# Sheet3.net
KiCad netlist of a schematic drawn in Altium Designer
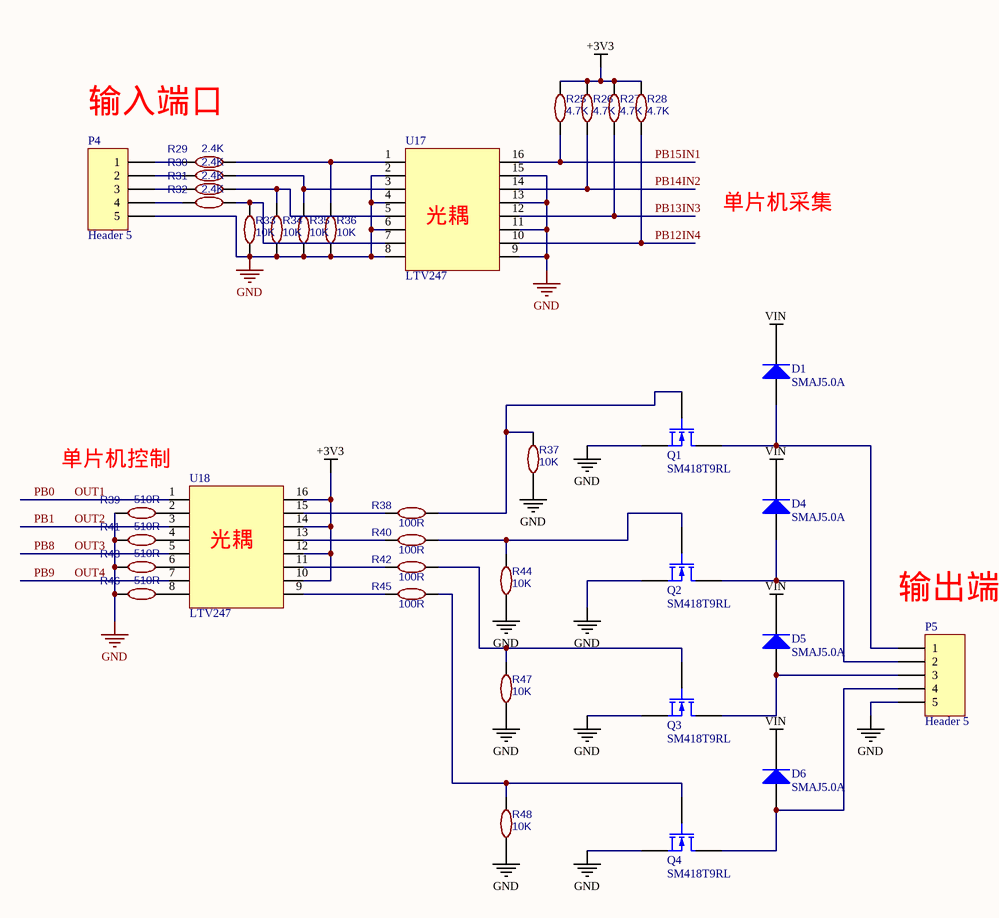
[diagram p0: Sheet3.SchDoc]

(export (version "E")
  (design (tool "Eeschema 10.0.6"))
  (components
    (comp (ref "D1")
      (value "SMAJ5.0A")
      (footprint "DO214-SMA-SOAC")
      (description "Default Diode")
      (fields (field (name "PUBLISHER") "Altium Limited"))
      (libsource (lib "Miscellaneous Devices") (part "Diode"))
    )
    (comp (ref "D4")
      (value "SMAJ5.0A")
      (footprint "DO214-SMA-SOAC")
      (description "Default Diode")
      (fields (field (name "PUBLISHER") "Altium Limited"))
      (libsource (lib "Miscellaneous Devices") (part "Diode"))
    )
    (comp (ref "D5")
      (value "SMAJ5.0A")
      (footprint "DO214-SMA-SOAC")
      (description "Default Diode")
      (fields (field (name "PUBLISHER") "Altium Limited"))
      (libsource (lib "Miscellaneous Devices") (part "Diode"))
    )
    (comp (ref "D6")
      (value "SMAJ5.0A")
      (footprint "DO214-SMA-SOAC")
      (description "Default Diode")
      (fields (field (name "PUBLISHER") "Altium Limited"))
      (libsource (lib "Miscellaneous Devices") (part "Diode"))
    )
    (comp (ref "P4")
      (value "Header 5")
      (footprint "HDR1X5")
      (description "Header, 5-Pin 隔离输入输出5P")
      (fields (field (name "PUBLISHER") "Altium Limited"))
      (libsource (lib "") (part "Header 5_1"))
    )
    (comp (ref "P5")
      (value "Header 5")
      (footprint "HDR1X5")
      (description "Header, 5-Pin 隔离输入输出5P")
      (fields (field (name "PUBLISHER") "Altium Limited"))
      (libsource (lib "Miscellaneous Connectors") (part "Header 5"))
    )
    (comp (ref "Q1")
      (value "SM418T9RL")
      (footprint "TO252-3")
      (description "N-Channel MOSFET")
      (fields (field (name "PUBLISHER") "Altium Limited"))
      (libsource (lib "Miscellaneous Devices") (part "MOSFET-N"))
    )
    (comp (ref "Q2")
      (value "SM418T9RL")
      (footprint "TO252-3")
      (description "N-Channel MOSFET")
      (fields (field (name "PUBLISHER") "Altium Limited"))
      (libsource (lib "Miscellaneous Devices") (part "MOSFET-N"))
    )
    (comp (ref "Q3")
      (value "SM418T9RL")
      (footprint "TO252-3")
      (description "N-Channel MOSFET")
      (fields (field (name "PUBLISHER") "Altium Limited"))
      (libsource (lib "Miscellaneous Devices") (part "MOSFET-N"))
    )
    (comp (ref "Q4")
      (value "SM418T9RL")
      (footprint "TO252-3")
      (description "N-Channel MOSFET")
      (fields (field (name "PUBLISHER") "Altium Limited"))
      (libsource (lib "Miscellaneous Devices") (part "MOSFET-N"))
    )
    (comp (ref "R25")
      (value "4.7K")
      (footprint "R0603")
      (fields
        (field (name "BOM_MANUFACTURER PART") "0603WAF1001T5E")
        (field (name "BOM_SUPPLIER PART") "C21190")
      )
      (libsource (lib "altium-import") (part "root_1_1K_"))
    )
    (comp (ref "R26")
      (value "4.7K")
      (footprint "R0603")
      (fields
        (field (name "BOM_MANUFACTURER PART") "0603WAF1001T5E")
        (field (name "BOM_SUPPLIER PART") "C21190")
      )
      (libsource (lib "altium-import") (part "root_1_1K_"))
    )
    (comp (ref "R27")
      (value "4.7K")
      (footprint "R0603")
      (fields
        (field (name "BOM_MANUFACTURER PART") "0603WAF1001T5E")
        (field (name "BOM_SUPPLIER PART") "C21190")
      )
      (libsource (lib "altium-import") (part "root_1_1K_"))
    )
    (comp (ref "R28")
      (value "4.7K")
      (footprint "R0603")
      (fields
        (field (name "BOM_MANUFACTURER PART") "0603WAF1001T5E")
        (field (name "BOM_SUPPLIER PART") "C21190")
      )
      (libsource (lib "altium-import") (part "root_1_1K_"))
    )
    (comp (ref "R29")
      (value "2.4K")
      (footprint "R0603")
      (fields
        (field (name "BOM_MANUFACTURER PART") "0603WAF1001T5E")
        (field (name "BOM_SUPPLIER PART") "C21190")
      )
      (libsource (lib "altium-import") (part "root_0_1K_"))
    )
    (comp (ref "R30")
      (value "2.4K")
      (footprint "R0603")
      (fields
        (field (name "BOM_MANUFACTURER PART") "0603WAF1001T5E")
        (field (name "BOM_SUPPLIER PART") "C21190")
      )
      (libsource (lib "altium-import") (part "root_0_1K_"))
    )
    (comp (ref "R31")
      (value "2.4K")
      (footprint "R0603")
      (fields
        (field (name "BOM_MANUFACTURER PART") "0603WAF1001T5E")
        (field (name "BOM_SUPPLIER PART") "C21190")
      )
      (libsource (lib "altium-import") (part "root_0_1K_"))
    )
    (comp (ref "R32")
      (value "2.4K")
      (footprint "R0603")
      (fields
        (field (name "BOM_MANUFACTURER PART") "0603WAF1001T5E")
        (field (name "BOM_SUPPLIER PART") "C21190")
      )
      (libsource (lib "altium-import") (part "root_0_1K_"))
    )
    (comp (ref "R33")
      (value "10K")
      (footprint "R0603")
      (fields
        (field (name "BOM_MANUFACTURER PART") "0603WAF1001T5E")
        (field (name "BOM_SUPPLIER PART") "C21190")
      )
      (libsource (lib "altium-import") (part "root_1_1K_"))
    )
    (comp (ref "R34")
      (value "10K")
      (footprint "R0603")
      (fields
        (field (name "BOM_MANUFACTURER PART") "0603WAF1001T5E")
        (field (name "BOM_SUPPLIER PART") "C21190")
      )
      (libsource (lib "altium-import") (part "root_1_1K_"))
    )
    (comp (ref "R35")
      (value "10K")
      (footprint "R0603")
      (fields
        (field (name "BOM_MANUFACTURER PART") "0603WAF1001T5E")
        (field (name "BOM_SUPPLIER PART") "C21190")
      )
      (libsource (lib "altium-import") (part "root_1_1K_"))
    )
    (comp (ref "R36")
      (value "10K")
      (footprint "R0603")
      (fields
        (field (name "BOM_MANUFACTURER PART") "0603WAF1001T5E")
        (field (name "BOM_SUPPLIER PART") "C21190")
      )
      (libsource (lib "altium-import") (part "root_1_1K_"))
    )
    (comp (ref "R37")
      (value "10K")
      (footprint "R0603")
      (fields
        (field (name "BOM_MANUFACTURER PART") "0603WAF1001T5E")
        (field (name "BOM_SUPPLIER PART") "C21190")
      )
      (libsource (lib "altium-import") (part "root_3_1K_"))
    )
    (comp (ref "R38")
      (value "100R")
      (footprint "R0603")
      (fields
        (field (name "BOM_MANUFACTURER PART") "0603WAF1001T5E")
        (field (name "BOM_SUPPLIER PART") "C21190")
      )
      (libsource (lib "altium-import") (part "root_0_1K_"))
    )
    (comp (ref "R39")
      (value "510R")
      (footprint "R0603")
      (fields
        (field (name "BOM_MANUFACTURER PART") "0603WAF1001T5E")
        (field (name "BOM_SUPPLIER PART") "C21190")
      )
      (libsource (lib "altium-import") (part "root_0_1K_"))
    )
    (comp (ref "R40")
      (value "100R")
      (footprint "R0603")
      (fields
        (field (name "BOM_MANUFACTURER PART") "0603WAF1001T5E")
        (field (name "BOM_SUPPLIER PART") "C21190")
      )
      (libsource (lib "altium-import") (part "root_0_1K_"))
    )
    (comp (ref "R41")
      (value "510R")
      (footprint "R0603")
      (fields
        (field (name "BOM_MANUFACTURER PART") "0603WAF1001T5E")
        (field (name "BOM_SUPPLIER PART") "C21190")
      )
      (libsource (lib "altium-import") (part "root_0_1K_"))
    )
    (comp (ref "R42")
      (value "100R")
      (footprint "R0603")
      (fields
        (field (name "BOM_MANUFACTURER PART") "0603WAF1001T5E")
        (field (name "BOM_SUPPLIER PART") "C21190")
      )
      (libsource (lib "altium-import") (part "root_0_1K_"))
    )
    (comp (ref "R43")
      (value "510R")
      (footprint "R0603")
      (fields
        (field (name "BOM_MANUFACTURER PART") "0603WAF1001T5E")
        (field (name "BOM_SUPPLIER PART") "C21190")
      )
      (libsource (lib "altium-import") (part "root_0_1K_"))
    )
    (comp (ref "R44")
      (value "10K")
      (footprint "R0603")
      (fields
        (field (name "BOM_MANUFACTURER PART") "0603WAF1001T5E")
        (field (name "BOM_SUPPLIER PART") "C21190")
      )
      (libsource (lib "altium-import") (part "root_3_1K_"))
    )
    (comp (ref "R45")
      (value "100R")
      (footprint "R0603")
      (fields
        (field (name "BOM_MANUFACTURER PART") "0603WAF1001T5E")
        (field (name "BOM_SUPPLIER PART") "C21190")
      )
      (libsource (lib "altium-import") (part "root_0_1K_"))
    )
    (comp (ref "R46")
      (value "510R")
      (footprint "R0603")
      (fields
        (field (name "BOM_MANUFACTURER PART") "0603WAF1001T5E")
        (field (name "BOM_SUPPLIER PART") "C21190")
      )
      (libsource (lib "altium-import") (part "root_0_1K_"))
    )
    (comp (ref "R47")
      (value "10K")
      (footprint "R0603")
      (fields
        (field (name "BOM_MANUFACTURER PART") "0603WAF1001T5E")
        (field (name "BOM_SUPPLIER PART") "C21190")
      )
      (libsource (lib "altium-import") (part "root_3_1K_"))
    )
    (comp (ref "R48")
      (value "10K")
      (footprint "R0603")
      (fields
        (field (name "BOM_MANUFACTURER PART") "0603WAF1001T5E")
        (field (name "BOM_SUPPLIER PART") "C21190")
      )
      (libsource (lib "altium-import") (part "root_3_1K_"))
    )
    (comp (ref "U17")
      (value "LTV247")
      (footprint "SOIC-16-M")
      (description "光耦")
      (libsource (lib "PCB_原理图库") (part "SOP-16"))
    )
    (comp (ref "U18")
      (value "LTV247")
      (footprint "SOIC-16-M")
      (description "光耦")
      (libsource (lib "PCB_原理图库") (part "SOP-16"))
    )
  )
  (nets
    (net (code "1") (name "+3V3") (class "Default")
      (node (ref "R25") (pin "2") (pinfunction "2_2") (pintype "passive"))
      (node (ref "R26") (pin "2") (pinfunction "2_2") (pintype "passive"))
      (node (ref "R27") (pin "2") (pinfunction "2_2") (pintype "passive"))
      (node (ref "R28") (pin "2") (pinfunction "2_2") (pintype "passive"))
      (node (ref "U18") (pin "10") (pinfunction "10_10") (pintype "passive"))
      (node (ref "U18") (pin "12") (pinfunction "12_12") (pintype "passive"))
      (node (ref "U18") (pin "14") (pinfunction "14_14") (pintype "passive"))
      (node (ref "U18") (pin "16") (pinfunction "16_16") (pintype "passive"))
    )
    (net (code "2") (name "/IN1") (class "Default")
      (node (ref "R25") (pin "1") (pinfunction "1_1") (pintype "passive"))
      (node (ref "U17") (pin "16") (pinfunction "16_16") (pintype "passive"))
    )
    (net (code "3") (name "/IN2") (class "Default")
      (node (ref "R26") (pin "1") (pinfunction "1_1") (pintype "passive"))
      (node (ref "U17") (pin "14") (pinfunction "14_14") (pintype "passive"))
    )
    (net (code "4") (name "/IN3") (class "Default")
      (node (ref "R27") (pin "1") (pinfunction "1_1") (pintype "passive"))
      (node (ref "U17") (pin "12") (pinfunction "12_12") (pintype "passive"))
    )
    (net (code "5") (name "/IN4") (class "Default")
      (node (ref "R28") (pin "1") (pinfunction "1_1") (pintype "passive"))
      (node (ref "U17") (pin "10") (pinfunction "10_10") (pintype "passive"))
    )
    (net (code "6") (name "/OUT1") (class "Default")
      (node (ref "U18") (pin "1") (pinfunction "1_1") (pintype "passive"))
    )
    (net (code "7") (name "/OUT2") (class "Default")
      (node (ref "U18") (pin "3") (pinfunction "3_3") (pintype "passive"))
    )
    (net (code "8") (name "/OUT3") (class "Default")
      (node (ref "U18") (pin "5") (pinfunction "5_5") (pintype "passive"))
    )
    (net (code "9") (name "/OUT4") (class "Default")
      (node (ref "U18") (pin "7") (pinfunction "7_7") (pintype "passive"))
    )
    (net (code "10") (name "GND") (class "Default")
      (node (ref "P4") (pin "5") (pinfunction "5_5") (pintype "passive"))
      (node (ref "P5") (pin "5") (pinfunction "5_5") (pintype "passive"))
      (node (ref "Q1") (pin "3") (pinfunction "S_3") (pintype "passive"))
      (node (ref "Q2") (pin "3") (pinfunction "S_3") (pintype "passive"))
      (node (ref "Q3") (pin "3") (pinfunction "S_3") (pintype "passive"))
      (node (ref "Q4") (pin "3") (pinfunction "S_3") (pintype "passive"))
      (node (ref "R33") (pin "1") (pinfunction "1_1") (pintype "passive"))
      (node (ref "R34") (pin "1") (pinfunction "1_1") (pintype "passive"))
      (node (ref "R35") (pin "1") (pinfunction "1_1") (pintype "passive"))
      (node (ref "R36") (pin "1") (pinfunction "1_1") (pintype "passive"))
      (node (ref "R37") (pin "2") (pinfunction "2_2") (pintype "passive"))
      (node (ref "R39") (pin "1") (pinfunction "1_1") (pintype "passive"))
      (node (ref "R41") (pin "1") (pinfunction "1_1") (pintype "passive"))
      (node (ref "R43") (pin "1") (pinfunction "1_1") (pintype "passive"))
      (node (ref "R44") (pin "2") (pinfunction "2_2") (pintype "passive"))
      (node (ref "R46") (pin "1") (pinfunction "1_1") (pintype "passive"))
      (node (ref "R47") (pin "2") (pinfunction "2_2") (pintype "passive"))
      (node (ref "R48") (pin "2") (pinfunction "2_2") (pintype "passive"))
      (node (ref "U17") (pin "11") (pinfunction "11_11") (pintype "passive"))
      (node (ref "U17") (pin "13") (pinfunction "13_13") (pintype "passive"))
      (node (ref "U17") (pin "15") (pinfunction "15_15") (pintype "passive"))
      (node (ref "U17") (pin "2") (pinfunction "2_2") (pintype "passive"))
      (node (ref "U17") (pin "4") (pinfunction "4_4") (pintype "passive"))
      (node (ref "U17") (pin "6") (pinfunction "6_6") (pintype "passive"))
      (node (ref "U17") (pin "8") (pinfunction "8_8") (pintype "passive"))
      (node (ref "U17") (pin "9") (pinfunction "9_9") (pintype "passive"))
    )
    (net (code "11") (name "Net-(D1-A)") (class "Default")
      (node (ref "D1") (pin "1") (pinfunction "A_1") (pintype "passive"))
      (node (ref "P5") (pin "1") (pinfunction "1_1") (pintype "passive"))
      (node (ref "Q1") (pin "1") (pinfunction "D_1") (pintype "passive"))
    )
    (net (code "12") (name "Net-(D4-A)") (class "Default")
      (node (ref "D4") (pin "1") (pinfunction "A_1") (pintype "passive"))
      (node (ref "P5") (pin "2") (pinfunction "2_2") (pintype "passive"))
      (node (ref "Q2") (pin "1") (pinfunction "D_1") (pintype "passive"))
    )
    (net (code "13") (name "Net-(D5-A)") (class "Default")
      (node (ref "D5") (pin "1") (pinfunction "A_1") (pintype "passive"))
      (node (ref "P5") (pin "3") (pinfunction "3_3") (pintype "passive"))
      (node (ref "Q3") (pin "1") (pinfunction "D_1") (pintype "passive"))
    )
    (net (code "14") (name "Net-(D6-A)") (class "Default")
      (node (ref "D6") (pin "1") (pinfunction "A_1") (pintype "passive"))
      (node (ref "P5") (pin "4") (pinfunction "4_4") (pintype "passive"))
      (node (ref "Q4") (pin "1") (pinfunction "D_1") (pintype "passive"))
    )
    (net (code "15") (name "Net-(P4-Pad1)") (class "Default")
      (node (ref "P4") (pin "1") (pinfunction "1_1") (pintype "passive"))
      (node (ref "R29") (pin "1") (pinfunction "1_1") (pintype "passive"))
    )
    (net (code "16") (name "Net-(P4-Pad2)") (class "Default")
      (node (ref "P4") (pin "2") (pinfunction "2_2") (pintype "passive"))
      (node (ref "R30") (pin "1") (pinfunction "1_1") (pintype "passive"))
    )
    (net (code "17") (name "Net-(P4-Pad3)") (class "Default")
      (node (ref "P4") (pin "3") (pinfunction "3_3") (pintype "passive"))
      (node (ref "R31") (pin "1") (pinfunction "1_1") (pintype "passive"))
    )
    (net (code "18") (name "Net-(P4-Pad4)") (class "Default")
      (node (ref "P4") (pin "4") (pinfunction "4_4") (pintype "passive"))
      (node (ref "R32") (pin "1") (pinfunction "1_1") (pintype "passive"))
    )
    (net (code "19") (name "Net-(Q1-G)") (class "Default")
      (node (ref "Q1") (pin "2") (pinfunction "G_2") (pintype "passive"))
      (node (ref "R37") (pin "1") (pinfunction "1_1") (pintype "passive"))
      (node (ref "R38") (pin "2") (pinfunction "2_2") (pintype "passive"))
    )
    (net (code "20") (name "Net-(Q2-G)") (class "Default")
      (node (ref "Q2") (pin "2") (pinfunction "G_2") (pintype "passive"))
      (node (ref "R40") (pin "2") (pinfunction "2_2") (pintype "passive"))
      (node (ref "R44") (pin "1") (pinfunction "1_1") (pintype "passive"))
    )
    (net (code "21") (name "Net-(Q3-G)") (class "Default")
      (node (ref "Q3") (pin "2") (pinfunction "G_2") (pintype "passive"))
      (node (ref "R42") (pin "2") (pinfunction "2_2") (pintype "passive"))
      (node (ref "R47") (pin "1") (pinfunction "1_1") (pintype "passive"))
    )
    (net (code "22") (name "Net-(Q4-G)") (class "Default")
      (node (ref "Q4") (pin "2") (pinfunction "G_2") (pintype "passive"))
      (node (ref "R45") (pin "2") (pinfunction "2_2") (pintype "passive"))
      (node (ref "R48") (pin "1") (pinfunction "1_1") (pintype "passive"))
    )
    (net (code "23") (name "Net-(R29-Pad2)") (class "Default")
      (node (ref "R29") (pin "2") (pinfunction "2_2") (pintype "passive"))
      (node (ref "R36") (pin "2") (pinfunction "2_2") (pintype "passive"))
      (node (ref "U17") (pin "1") (pinfunction "1_1") (pintype "passive"))
    )
    (net (code "24") (name "Net-(R30-Pad2)") (class "Default")
      (node (ref "R30") (pin "2") (pinfunction "2_2") (pintype "passive"))
      (node (ref "R35") (pin "2") (pinfunction "2_2") (pintype "passive"))
      (node (ref "U17") (pin "3") (pinfunction "3_3") (pintype "passive"))
    )
    (net (code "25") (name "Net-(R31-Pad2)") (class "Default")
      (node (ref "R31") (pin "2") (pinfunction "2_2") (pintype "passive"))
      (node (ref "R34") (pin "2") (pinfunction "2_2") (pintype "passive"))
      (node (ref "U17") (pin "5") (pinfunction "5_5") (pintype "passive"))
    )
    (net (code "26") (name "Net-(R32-Pad2)") (class "Default")
      (node (ref "R32") (pin "2") (pinfunction "2_2") (pintype "passive"))
      (node (ref "R33") (pin "2") (pinfunction "2_2") (pintype "passive"))
      (node (ref "U17") (pin "7") (pinfunction "7_7") (pintype "passive"))
    )
    (net (code "27") (name "Net-(R38-Pad1)") (class "Default")
      (node (ref "R38") (pin "1") (pinfunction "1_1") (pintype "passive"))
      (node (ref "U18") (pin "15") (pinfunction "15_15") (pintype "passive"))
    )
    (net (code "28") (name "Net-(R39-Pad2)") (class "Default")
      (node (ref "R39") (pin "2") (pinfunction "2_2") (pintype "passive"))
      (node (ref "U18") (pin "2") (pinfunction "2_2") (pintype "passive"))
    )
    (net (code "29") (name "Net-(R40-Pad1)") (class "Default")
      (node (ref "R40") (pin "1") (pinfunction "1_1") (pintype "passive"))
      (node (ref "U18") (pin "13") (pinfunction "13_13") (pintype "passive"))
    )
    (net (code "30") (name "Net-(R41-Pad2)") (class "Default")
      (node (ref "R41") (pin "2") (pinfunction "2_2") (pintype "passive"))
      (node (ref "U18") (pin "4") (pinfunction "4_4") (pintype "passive"))
    )
    (net (code "31") (name "Net-(R42-Pad1)") (class "Default")
      (node (ref "R42") (pin "1") (pinfunction "1_1") (pintype "passive"))
      (node (ref "U18") (pin "11") (pinfunction "11_11") (pintype "passive"))
    )
    (net (code "32") (name "Net-(R43-Pad2)") (class "Default")
      (node (ref "R43") (pin "2") (pinfunction "2_2") (pintype "passive"))
      (node (ref "U18") (pin "6") (pinfunction "6_6") (pintype "passive"))
    )
    (net (code "33") (name "Net-(R45-Pad1)") (class "Default")
      (node (ref "R45") (pin "1") (pinfunction "1_1") (pintype "passive"))
      (node (ref "U18") (pin "9") (pinfunction "9_9") (pintype "passive"))
    )
    (net (code "34") (name "Net-(R46-Pad2)") (class "Default")
      (node (ref "R46") (pin "2") (pinfunction "2_2") (pintype "passive"))
      (node (ref "U18") (pin "8") (pinfunction "8_8") (pintype "passive"))
    )
    (net (code "35") (name "VIN") (class "Default")
      (node (ref "D1") (pin "2") (pinfunction "K_2") (pintype "passive"))
      (node (ref "D4") (pin "2") (pinfunction "K_2") (pintype "passive"))
      (node (ref "D5") (pin "2") (pinfunction "K_2") (pintype "passive"))
      (node (ref "D6") (pin "2") (pinfunction "K_2") (pintype "passive"))
    )
  )
)
